# BATT_DISP_v7.net
KiCad netlist of a schematic drawn in EAGLE
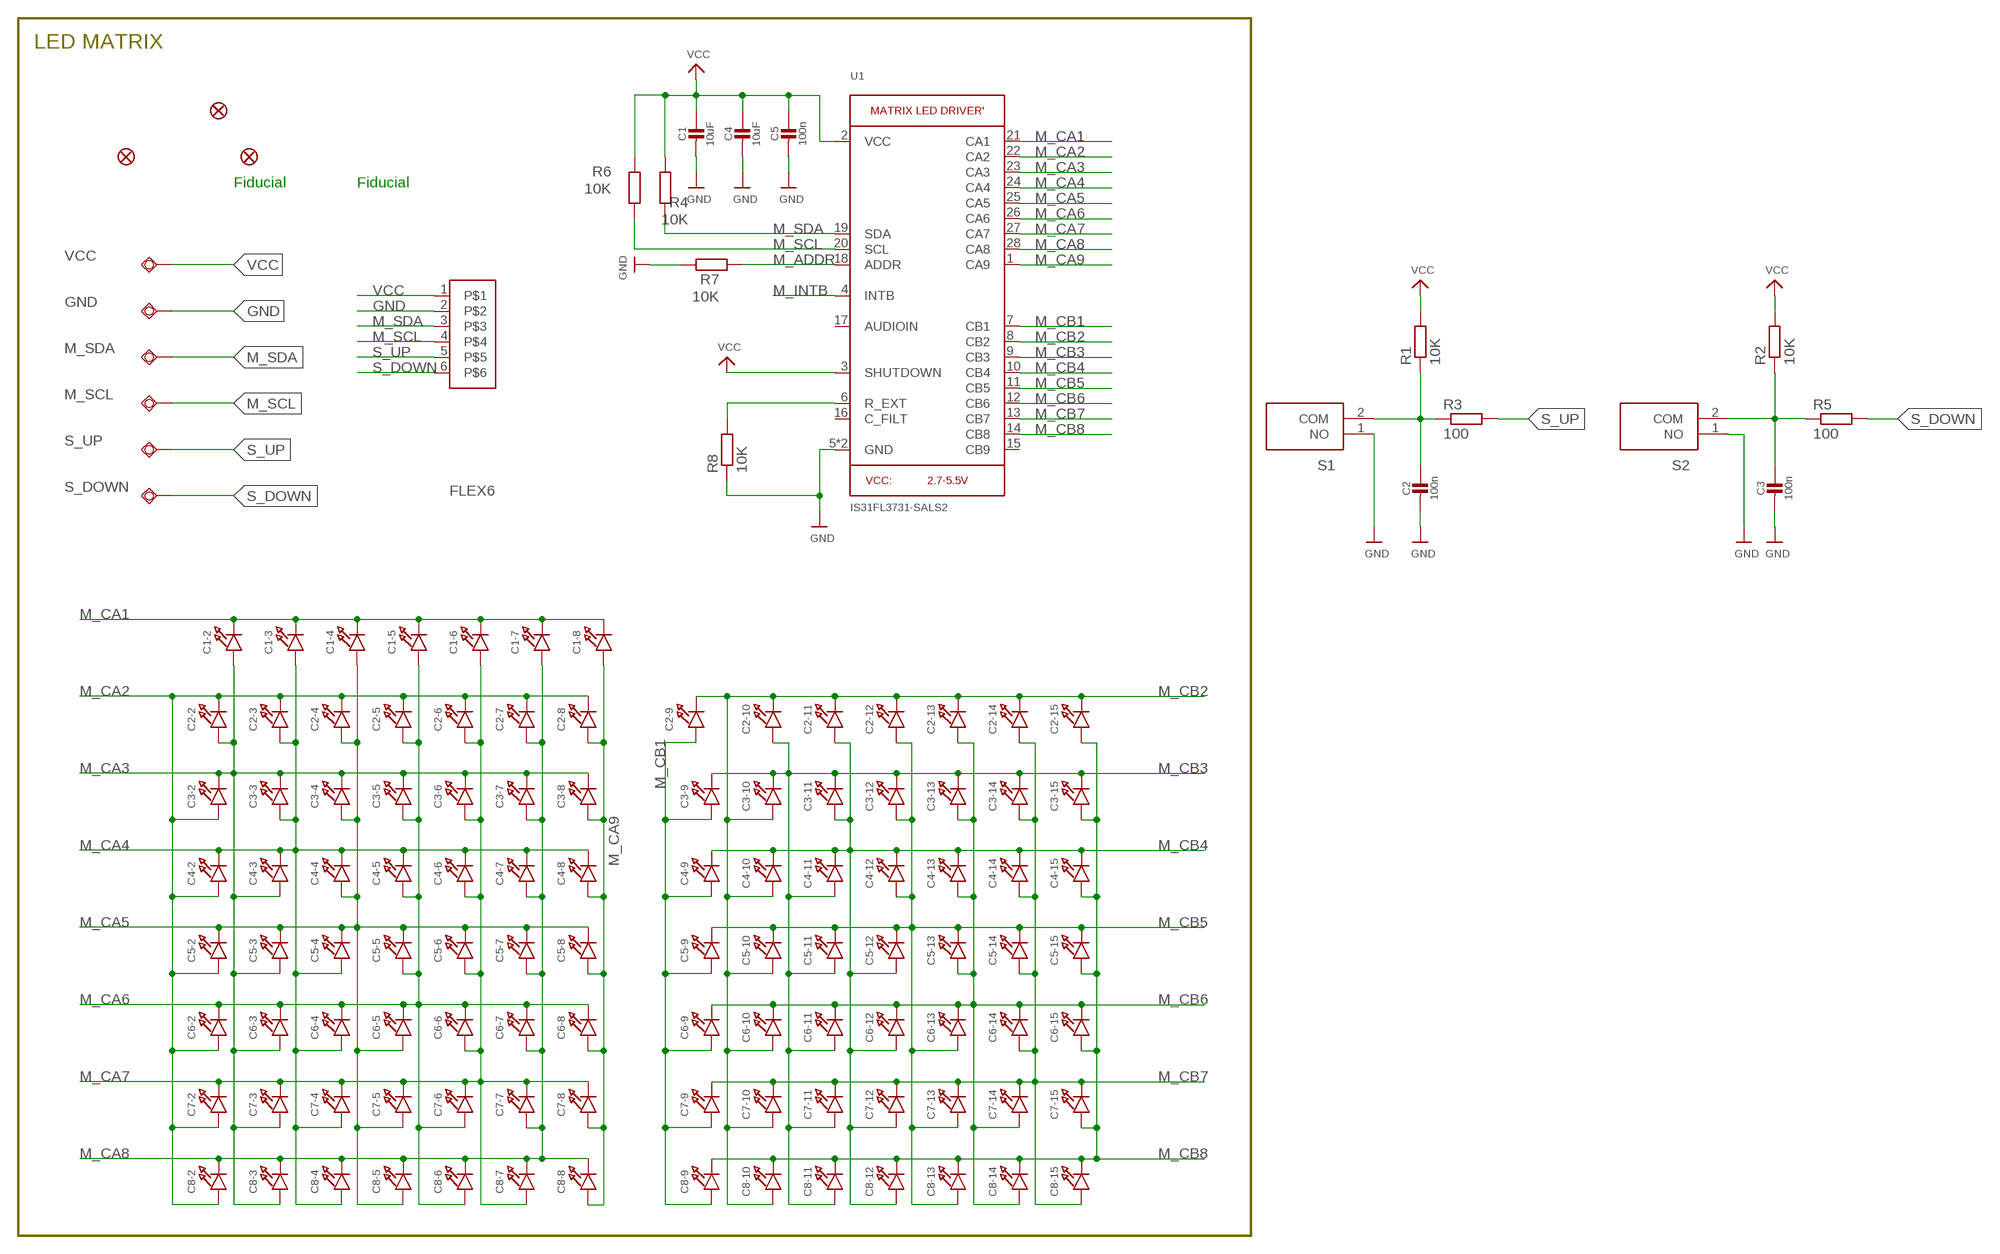
[diagram p0: schematic, sheet 1]

(export (version "E")
  (design (tool "Eeschema 10.0.6"))
  (components
    (comp (ref "C1")
      (value "10uF")
      (footprint "eagle-import:0805-NO")
      (libsource (lib "eagle-import") (part "CAP_CERAMIC0805-NOOUTLINE"))
    )
    (comp (ref "C1-2")
      (value "LED0402_NOOUTLINE")
      (footprint "eagle-import:CHIPLED_0402_NOOUTLINE")
      (libsource (lib "eagle-import") (part "LED0402_NOOUTLINE"))
    )
    (comp (ref "C1-3")
      (value "LED0402_NOOUTLINE")
      (footprint "eagle-import:CHIPLED_0402_NOOUTLINE")
      (libsource (lib "eagle-import") (part "LED0402_NOOUTLINE"))
    )
    (comp (ref "C1-4")
      (value "LED0402_NOOUTLINE")
      (footprint "eagle-import:CHIPLED_0402_NOOUTLINE")
      (libsource (lib "eagle-import") (part "LED0402_NOOUTLINE"))
    )
    (comp (ref "C1-5")
      (value "LED0402_NOOUTLINE")
      (footprint "eagle-import:CHIPLED_0402_NOOUTLINE")
      (libsource (lib "eagle-import") (part "LED0402_NOOUTLINE"))
    )
    (comp (ref "C1-6")
      (value "LED0402_NOOUTLINE")
      (footprint "eagle-import:CHIPLED_0402_NOOUTLINE")
      (libsource (lib "eagle-import") (part "LED0402_NOOUTLINE"))
    )
    (comp (ref "C1-7")
      (value "LED0402_NOOUTLINE")
      (footprint "eagle-import:CHIPLED_0402_NOOUTLINE")
      (libsource (lib "eagle-import") (part "LED0402_NOOUTLINE"))
    )
    (comp (ref "C1-8")
      (value "LED0402_NOOUTLINE")
      (footprint "eagle-import:CHIPLED_0402_NOOUTLINE")
      (libsource (lib "eagle-import") (part "LED0402_NOOUTLINE"))
    )
    (comp (ref "C2")
      (value "100n")
      (footprint "eagle-import:0805-NO")
      (libsource (lib "eagle-import") (part "CAP_CERAMIC0805-NOOUTLINE"))
    )
    (comp (ref "C2-2")
      (value "LED0402_NOOUTLINE")
      (footprint "eagle-import:CHIPLED_0402_NOOUTLINE")
      (libsource (lib "eagle-import") (part "LED0402_NOOUTLINE"))
    )
    (comp (ref "C2-3")
      (value "LED0402_NOOUTLINE")
      (footprint "eagle-import:CHIPLED_0402_NOOUTLINE")
      (libsource (lib "eagle-import") (part "LED0402_NOOUTLINE"))
    )
    (comp (ref "C2-4")
      (value "LED0402_NOOUTLINE")
      (footprint "eagle-import:CHIPLED_0402_NOOUTLINE")
      (libsource (lib "eagle-import") (part "LED0402_NOOUTLINE"))
    )
    (comp (ref "C2-5")
      (value "LED0402_NOOUTLINE")
      (footprint "eagle-import:CHIPLED_0402_NOOUTLINE")
      (libsource (lib "eagle-import") (part "LED0402_NOOUTLINE"))
    )
    (comp (ref "C2-6")
      (value "LED0402_NOOUTLINE")
      (footprint "eagle-import:CHIPLED_0402_NOOUTLINE")
      (libsource (lib "eagle-import") (part "LED0402_NOOUTLINE"))
    )
    (comp (ref "C2-7")
      (value "LED0402_NOOUTLINE")
      (footprint "eagle-import:CHIPLED_0402_NOOUTLINE")
      (libsource (lib "eagle-import") (part "LED0402_NOOUTLINE"))
    )
    (comp (ref "C2-8")
      (value "LED0402_NOOUTLINE")
      (footprint "eagle-import:CHIPLED_0402_NOOUTLINE")
      (libsource (lib "eagle-import") (part "LED0402_NOOUTLINE"))
    )
    (comp (ref "C2-9")
      (value "LED0402_NOOUTLINE")
      (footprint "eagle-import:CHIPLED_0402_NOOUTLINE")
      (libsource (lib "eagle-import") (part "LED0402_NOOUTLINE"))
    )
    (comp (ref "C2-10")
      (value "LED0402_NOOUTLINE")
      (footprint "eagle-import:CHIPLED_0402_NOOUTLINE")
      (libsource (lib "eagle-import") (part "LED0402_NOOUTLINE"))
    )
    (comp (ref "C2-11")
      (value "LED0402_NOOUTLINE")
      (footprint "eagle-import:CHIPLED_0402_NOOUTLINE")
      (libsource (lib "eagle-import") (part "LED0402_NOOUTLINE"))
    )
    (comp (ref "C2-12")
      (value "LED0402_NOOUTLINE")
      (footprint "eagle-import:CHIPLED_0402_NOOUTLINE")
      (libsource (lib "eagle-import") (part "LED0402_NOOUTLINE"))
    )
    (comp (ref "C2-13")
      (value "LED0402_NOOUTLINE")
      (footprint "eagle-import:CHIPLED_0402_NOOUTLINE")
      (libsource (lib "eagle-import") (part "LED0402_NOOUTLINE"))
    )
    (comp (ref "C2-14")
      (value "LED0402_NOOUTLINE")
      (footprint "eagle-import:CHIPLED_0402_NOOUTLINE")
      (libsource (lib "eagle-import") (part "LED0402_NOOUTLINE"))
    )
    (comp (ref "C2-15")
      (value "LED0402_NOOUTLINE")
      (footprint "eagle-import:CHIPLED_0402_NOOUTLINE")
      (libsource (lib "eagle-import") (part "LED0402_NOOUTLINE"))
    )
    (comp (ref "C3")
      (value "100n")
      (footprint "eagle-import:0805-NO")
      (libsource (lib "eagle-import") (part "CAP_CERAMIC0805-NOOUTLINE"))
    )
    (comp (ref "C3-2")
      (value "LED0402_NOOUTLINE")
      (footprint "eagle-import:CHIPLED_0402_NOOUTLINE")
      (libsource (lib "eagle-import") (part "LED0402_NOOUTLINE"))
    )
    (comp (ref "C3-3")
      (value "LED0402_NOOUTLINE")
      (footprint "eagle-import:CHIPLED_0402_NOOUTLINE")
      (libsource (lib "eagle-import") (part "LED0402_NOOUTLINE"))
    )
    (comp (ref "C3-4")
      (value "LED0402_NOOUTLINE")
      (footprint "eagle-import:CHIPLED_0402_NOOUTLINE")
      (libsource (lib "eagle-import") (part "LED0402_NOOUTLINE"))
    )
    (comp (ref "C3-5")
      (value "LED0402_NOOUTLINE")
      (footprint "eagle-import:CHIPLED_0402_NOOUTLINE")
      (libsource (lib "eagle-import") (part "LED0402_NOOUTLINE"))
    )
    (comp (ref "C3-6")
      (value "LED0402_NOOUTLINE")
      (footprint "eagle-import:CHIPLED_0402_NOOUTLINE")
      (libsource (lib "eagle-import") (part "LED0402_NOOUTLINE"))
    )
    (comp (ref "C3-7")
      (value "LED0402_NOOUTLINE")
      (footprint "eagle-import:CHIPLED_0402_NOOUTLINE")
      (libsource (lib "eagle-import") (part "LED0402_NOOUTLINE"))
    )
    (comp (ref "C3-8")
      (value "LED0402_NOOUTLINE")
      (footprint "eagle-import:CHIPLED_0402_NOOUTLINE")
      (libsource (lib "eagle-import") (part "LED0402_NOOUTLINE"))
    )
    (comp (ref "C3-9")
      (value "LED0402_NOOUTLINE")
      (footprint "eagle-import:CHIPLED_0402_NOOUTLINE")
      (libsource (lib "eagle-import") (part "LED0402_NOOUTLINE"))
    )
    (comp (ref "C3-10")
      (value "LED0402_NOOUTLINE")
      (footprint "eagle-import:CHIPLED_0402_NOOUTLINE")
      (libsource (lib "eagle-import") (part "LED0402_NOOUTLINE"))
    )
    (comp (ref "C3-11")
      (value "LED0402_NOOUTLINE")
      (footprint "eagle-import:CHIPLED_0402_NOOUTLINE")
      (libsource (lib "eagle-import") (part "LED0402_NOOUTLINE"))
    )
    (comp (ref "C3-12")
      (value "LED0402_NOOUTLINE")
      (footprint "eagle-import:CHIPLED_0402_NOOUTLINE")
      (libsource (lib "eagle-import") (part "LED0402_NOOUTLINE"))
    )
    (comp (ref "C3-13")
      (value "LED0402_NOOUTLINE")
      (footprint "eagle-import:CHIPLED_0402_NOOUTLINE")
      (libsource (lib "eagle-import") (part "LED0402_NOOUTLINE"))
    )
    (comp (ref "C3-14")
      (value "LED0402_NOOUTLINE")
      (footprint "eagle-import:CHIPLED_0402_NOOUTLINE")
      (libsource (lib "eagle-import") (part "LED0402_NOOUTLINE"))
    )
    (comp (ref "C3-15")
      (value "LED0402_NOOUTLINE")
      (footprint "eagle-import:CHIPLED_0402_NOOUTLINE")
      (libsource (lib "eagle-import") (part "LED0402_NOOUTLINE"))
    )
    (comp (ref "C4")
      (value "10uF")
      (footprint "eagle-import:0805-NO")
      (libsource (lib "eagle-import") (part "CAP_CERAMIC0805-NOOUTLINE"))
    )
    (comp (ref "C4-2")
      (value "LED0402_NOOUTLINE")
      (footprint "eagle-import:CHIPLED_0402_NOOUTLINE")
      (libsource (lib "eagle-import") (part "LED0402_NOOUTLINE"))
    )
    (comp (ref "C4-3")
      (value "LED0402_NOOUTLINE")
      (footprint "eagle-import:CHIPLED_0402_NOOUTLINE")
      (libsource (lib "eagle-import") (part "LED0402_NOOUTLINE"))
    )
    (comp (ref "C4-4")
      (value "LED0402_NOOUTLINE")
      (footprint "eagle-import:CHIPLED_0402_NOOUTLINE")
      (libsource (lib "eagle-import") (part "LED0402_NOOUTLINE"))
    )
    (comp (ref "C4-5")
      (value "LED0402_NOOUTLINE")
      (footprint "eagle-import:CHIPLED_0402_NOOUTLINE")
      (libsource (lib "eagle-import") (part "LED0402_NOOUTLINE"))
    )
    (comp (ref "C4-6")
      (value "LED0402_NOOUTLINE")
      (footprint "eagle-import:CHIPLED_0402_NOOUTLINE")
      (libsource (lib "eagle-import") (part "LED0402_NOOUTLINE"))
    )
    (comp (ref "C4-7")
      (value "LED0402_NOOUTLINE")
      (footprint "eagle-import:CHIPLED_0402_NOOUTLINE")
      (libsource (lib "eagle-import") (part "LED0402_NOOUTLINE"))
    )
    (comp (ref "C4-8")
      (value "LED0402_NOOUTLINE")
      (footprint "eagle-import:CHIPLED_0402_NOOUTLINE")
      (libsource (lib "eagle-import") (part "LED0402_NOOUTLINE"))
    )
    (comp (ref "C4-9")
      (value "LED0402_NOOUTLINE")
      (footprint "eagle-import:CHIPLED_0402_NOOUTLINE")
      (libsource (lib "eagle-import") (part "LED0402_NOOUTLINE"))
    )
    (comp (ref "C4-10")
      (value "LED0402_NOOUTLINE")
      (footprint "eagle-import:CHIPLED_0402_NOOUTLINE")
      (libsource (lib "eagle-import") (part "LED0402_NOOUTLINE"))
    )
    (comp (ref "C4-11")
      (value "LED0402_NOOUTLINE")
      (footprint "eagle-import:CHIPLED_0402_NOOUTLINE")
      (libsource (lib "eagle-import") (part "LED0402_NOOUTLINE"))
    )
    (comp (ref "C4-12")
      (value "LED0402_NOOUTLINE")
      (footprint "eagle-import:CHIPLED_0402_NOOUTLINE")
      (libsource (lib "eagle-import") (part "LED0402_NOOUTLINE"))
    )
    (comp (ref "C4-13")
      (value "LED0402_NOOUTLINE")
      (footprint "eagle-import:CHIPLED_0402_NOOUTLINE")
      (libsource (lib "eagle-import") (part "LED0402_NOOUTLINE"))
    )
    (comp (ref "C4-14")
      (value "LED0402_NOOUTLINE")
      (footprint "eagle-import:CHIPLED_0402_NOOUTLINE")
      (libsource (lib "eagle-import") (part "LED0402_NOOUTLINE"))
    )
    (comp (ref "C4-15")
      (value "LED0402_NOOUTLINE")
      (footprint "eagle-import:CHIPLED_0402_NOOUTLINE")
      (libsource (lib "eagle-import") (part "LED0402_NOOUTLINE"))
    )
    (comp (ref "C5")
      (value "100n")
      (footprint "eagle-import:0805-NO")
      (libsource (lib "eagle-import") (part "CAP_CERAMIC0805-NOOUTLINE"))
    )
    (comp (ref "C5-2")
      (value "LED0402_NOOUTLINE")
      (footprint "eagle-import:CHIPLED_0402_NOOUTLINE")
      (libsource (lib "eagle-import") (part "LED0402_NOOUTLINE"))
    )
    (comp (ref "C5-3")
      (value "LED0402_NOOUTLINE")
      (footprint "eagle-import:CHIPLED_0402_NOOUTLINE")
      (libsource (lib "eagle-import") (part "LED0402_NOOUTLINE"))
    )
    (comp (ref "C5-4")
      (value "LED0402_NOOUTLINE")
      (footprint "eagle-import:CHIPLED_0402_NOOUTLINE")
      (libsource (lib "eagle-import") (part "LED0402_NOOUTLINE"))
    )
    (comp (ref "C5-5")
      (value "LED0402_NOOUTLINE")
      (footprint "eagle-import:CHIPLED_0402_NOOUTLINE")
      (libsource (lib "eagle-import") (part "LED0402_NOOUTLINE"))
    )
    (comp (ref "C5-6")
      (value "LED0402_NOOUTLINE")
      (footprint "eagle-import:CHIPLED_0402_NOOUTLINE")
      (libsource (lib "eagle-import") (part "LED0402_NOOUTLINE"))
    )
    (comp (ref "C5-7")
      (value "LED0402_NOOUTLINE")
      (footprint "eagle-import:CHIPLED_0402_NOOUTLINE")
      (libsource (lib "eagle-import") (part "LED0402_NOOUTLINE"))
    )
    (comp (ref "C5-8")
      (value "LED0402_NOOUTLINE")
      (footprint "eagle-import:CHIPLED_0402_NOOUTLINE")
      (libsource (lib "eagle-import") (part "LED0402_NOOUTLINE"))
    )
    (comp (ref "C5-9")
      (value "LED0402_NOOUTLINE")
      (footprint "eagle-import:CHIPLED_0402_NOOUTLINE")
      (libsource (lib "eagle-import") (part "LED0402_NOOUTLINE"))
    )
    (comp (ref "C5-10")
      (value "LED0402_NOOUTLINE")
      (footprint "eagle-import:CHIPLED_0402_NOOUTLINE")
      (libsource (lib "eagle-import") (part "LED0402_NOOUTLINE"))
    )
    (comp (ref "C5-11")
      (value "LED0402_NOOUTLINE")
      (footprint "eagle-import:CHIPLED_0402_NOOUTLINE")
      (libsource (lib "eagle-import") (part "LED0402_NOOUTLINE"))
    )
    (comp (ref "C5-12")
      (value "LED0402_NOOUTLINE")
      (footprint "eagle-import:CHIPLED_0402_NOOUTLINE")
      (libsource (lib "eagle-import") (part "LED0402_NOOUTLINE"))
    )
    (comp (ref "C5-13")
      (value "LED0402_NOOUTLINE")
      (footprint "eagle-import:CHIPLED_0402_NOOUTLINE")
      (libsource (lib "eagle-import") (part "LED0402_NOOUTLINE"))
    )
    (comp (ref "C5-14")
      (value "LED0402_NOOUTLINE")
      (footprint "eagle-import:CHIPLED_0402_NOOUTLINE")
      (libsource (lib "eagle-import") (part "LED0402_NOOUTLINE"))
    )
    (comp (ref "C5-15")
      (value "LED0402_NOOUTLINE")
      (footprint "eagle-import:CHIPLED_0402_NOOUTLINE")
      (libsource (lib "eagle-import") (part "LED0402_NOOUTLINE"))
    )
    (comp (ref "C6-2")
      (value "LED0402_NOOUTLINE")
      (footprint "eagle-import:CHIPLED_0402_NOOUTLINE")
      (libsource (lib "eagle-import") (part "LED0402_NOOUTLINE"))
    )
    (comp (ref "C6-3")
      (value "LED0402_NOOUTLINE")
      (footprint "eagle-import:CHIPLED_0402_NOOUTLINE")
      (libsource (lib "eagle-import") (part "LED0402_NOOUTLINE"))
    )
    (comp (ref "C6-4")
      (value "LED0402_NOOUTLINE")
      (footprint "eagle-import:CHIPLED_0402_NOOUTLINE")
      (libsource (lib "eagle-import") (part "LED0402_NOOUTLINE"))
    )
    (comp (ref "C6-5")
      (value "LED0402_NOOUTLINE")
      (footprint "eagle-import:CHIPLED_0402_NOOUTLINE")
      (libsource (lib "eagle-import") (part "LED0402_NOOUTLINE"))
    )
    (comp (ref "C6-6")
      (value "LED0402_NOOUTLINE")
      (footprint "eagle-import:CHIPLED_0402_NOOUTLINE")
      (libsource (lib "eagle-import") (part "LED0402_NOOUTLINE"))
    )
    (comp (ref "C6-7")
      (value "LED0402_NOOUTLINE")
      (footprint "eagle-import:CHIPLED_0402_NOOUTLINE")
      (libsource (lib "eagle-import") (part "LED0402_NOOUTLINE"))
    )
    (comp (ref "C6-8")
      (value "LED0402_NOOUTLINE")
      (footprint "eagle-import:CHIPLED_0402_NOOUTLINE")
      (libsource (lib "eagle-import") (part "LED0402_NOOUTLINE"))
    )
    (comp (ref "C6-9")
      (value "LED0402_NOOUTLINE")
      (footprint "eagle-import:CHIPLED_0402_NOOUTLINE")
      (libsource (lib "eagle-import") (part "LED0402_NOOUTLINE"))
    )
    (comp (ref "C6-10")
      (value "LED0402_NOOUTLINE")
      (footprint "eagle-import:CHIPLED_0402_NOOUTLINE")
      (libsource (lib "eagle-import") (part "LED0402_NOOUTLINE"))
    )
    (comp (ref "C6-11")
      (value "LED0402_NOOUTLINE")
      (footprint "eagle-import:CHIPLED_0402_NOOUTLINE")
      (libsource (lib "eagle-import") (part "LED0402_NOOUTLINE"))
    )
    (comp (ref "C6-12")
      (value "LED0402_NOOUTLINE")
      (footprint "eagle-import:CHIPLED_0402_NOOUTLINE")
      (libsource (lib "eagle-import") (part "LED0402_NOOUTLINE"))
    )
    (comp (ref "C6-13")
      (value "LED0402_NOOUTLINE")
      (footprint "eagle-import:CHIPLED_0402_NOOUTLINE")
      (libsource (lib "eagle-import") (part "LED0402_NOOUTLINE"))
    )
    (comp (ref "C6-14")
      (value "LED0402_NOOUTLINE")
      (footprint "eagle-import:CHIPLED_0402_NOOUTLINE")
      (libsource (lib "eagle-import") (part "LED0402_NOOUTLINE"))
    )
    (comp (ref "C6-15")
      (value "LED0402_NOOUTLINE")
      (footprint "eagle-import:CHIPLED_0402_NOOUTLINE")
      (libsource (lib "eagle-import") (part "LED0402_NOOUTLINE"))
    )
    (comp (ref "C7-2")
      (value "LED0402_NOOUTLINE")
      (footprint "eagle-import:CHIPLED_0402_NOOUTLINE")
      (libsource (lib "eagle-import") (part "LED0402_NOOUTLINE"))
    )
    (comp (ref "C7-3")
      (value "LED0402_NOOUTLINE")
      (footprint "eagle-import:CHIPLED_0402_NOOUTLINE")
      (libsource (lib "eagle-import") (part "LED0402_NOOUTLINE"))
    )
    (comp (ref "C7-4")
      (value "LED0402_NOOUTLINE")
      (footprint "eagle-import:CHIPLED_0402_NOOUTLINE")
      (libsource (lib "eagle-import") (part "LED0402_NOOUTLINE"))
    )
    (comp (ref "C7-5")
      (value "LED0402_NOOUTLINE")
      (footprint "eagle-import:CHIPLED_0402_NOOUTLINE")
      (libsource (lib "eagle-import") (part "LED0402_NOOUTLINE"))
    )
    (comp (ref "C7-6")
      (value "LED0402_NOOUTLINE")
      (footprint "eagle-import:CHIPLED_0402_NOOUTLINE")
      (libsource (lib "eagle-import") (part "LED0402_NOOUTLINE"))
    )
    (comp (ref "C7-7")
      (value "LED0402_NOOUTLINE")
      (footprint "eagle-import:CHIPLED_0402_NOOUTLINE")
      (libsource (lib "eagle-import") (part "LED0402_NOOUTLINE"))
    )
    (comp (ref "C7-8")
      (value "LED0402_NOOUTLINE")
      (footprint "eagle-import:CHIPLED_0402_NOOUTLINE")
      (libsource (lib "eagle-import") (part "LED0402_NOOUTLINE"))
    )
    (comp (ref "C7-9")
      (value "LED0402_NOOUTLINE")
      (footprint "eagle-import:CHIPLED_0402_NOOUTLINE")
      (libsource (lib "eagle-import") (part "LED0402_NOOUTLINE"))
    )
    (comp (ref "C7-10")
      (value "LED0402_NOOUTLINE")
      (footprint "eagle-import:CHIPLED_0402_NOOUTLINE")
      (libsource (lib "eagle-import") (part "LED0402_NOOUTLINE"))
    )
    (comp (ref "C7-11")
      (value "LED0402_NOOUTLINE")
      (footprint "eagle-import:CHIPLED_0402_NOOUTLINE")
      (libsource (lib "eagle-import") (part "LED0402_NOOUTLINE"))
    )
    (comp (ref "C7-12")
      (value "LED0402_NOOUTLINE")
      (footprint "eagle-import:CHIPLED_0402_NOOUTLINE")
      (libsource (lib "eagle-import") (part "LED0402_NOOUTLINE"))
    )
    (comp (ref "C7-13")
      (value "LED0402_NOOUTLINE")
      (footprint "eagle-import:CHIPLED_0402_NOOUTLINE")
      (libsource (lib "eagle-import") (part "LED0402_NOOUTLINE"))
    )
    (comp (ref "C7-14")
      (value "LED0402_NOOUTLINE")
      (footprint "eagle-import:CHIPLED_0402_NOOUTLINE")
      (libsource (lib "eagle-import") (part "LED0402_NOOUTLINE"))
    )
    (comp (ref "C7-15")
      (value "LED0402_NOOUTLINE")
      (footprint "eagle-import:CHIPLED_0402_NOOUTLINE")
      (libsource (lib "eagle-import") (part "LED0402_NOOUTLINE"))
    )
    (comp (ref "C8-2")
      (value "LED0402_NOOUTLINE")
      (footprint "eagle-import:CHIPLED_0402_NOOUTLINE")
      (libsource (lib "eagle-import") (part "LED0402_NOOUTLINE"))
    )
    (comp (ref "C8-3")
      (value "LED0402_NOOUTLINE")
      (footprint "eagle-import:CHIPLED_0402_NOOUTLINE")
      (libsource (lib "eagle-import") (part "LED0402_NOOUTLINE"))
    )
    (comp (ref "C8-4")
      (value "LED0402_NOOUTLINE")
      (footprint "eagle-import:CHIPLED_0402_NOOUTLINE")
      (libsource (lib "eagle-import") (part "LED0402_NOOUTLINE"))
    )
    (comp (ref "C8-5")
      (value "LED0402_NOOUTLINE")
      (footprint "eagle-import:CHIPLED_0402_NOOUTLINE")
      (libsource (lib "eagle-import") (part "LED0402_NOOUTLINE"))
    )
    (comp (ref "C8-6")
      (value "LED0402_NOOUTLINE")
      (footprint "eagle-import:CHIPLED_0402_NOOUTLINE")
      (libsource (lib "eagle-import") (part "LED0402_NOOUTLINE"))
    )
    (comp (ref "C8-7")
      (value "LED0402_NOOUTLINE")
      (footprint "eagle-import:CHIPLED_0402_NOOUTLINE")
      (libsource (lib "eagle-import") (part "LED0402_NOOUTLINE"))
    )
    (comp (ref "C8-8")
      (value "LED0402_NOOUTLINE")
      (footprint "eagle-import:CHIPLED_0402_NOOUTLINE")
      (libsource (lib "eagle-import") (part "LED0402_NOOUTLINE"))
    )
    (comp (ref "C8-9")
      (value "LED0402_NOOUTLINE")
      (footprint "eagle-import:CHIPLED_0402_NOOUTLINE")
      (libsource (lib "eagle-import") (part "LED0402_NOOUTLINE"))
    )
    (comp (ref "C8-10")
      (value "LED0402_NOOUTLINE")
      (footprint "eagle-import:CHIPLED_0402_NOOUTLINE")
      (libsource (lib "eagle-import") (part "LED0402_NOOUTLINE"))
    )
    (comp (ref "C8-11")
      (value "LED0402_NOOUTLINE")
      (footprint "eagle-import:CHIPLED_0402_NOOUTLINE")
      (libsource (lib "eagle-import") (part "LED0402_NOOUTLINE"))
    )
    (comp (ref "C8-12")
      (value "LED0402_NOOUTLINE")
      (footprint "eagle-import:CHIPLED_0402_NOOUTLINE")
      (libsource (lib "eagle-import") (part "LED0402_NOOUTLINE"))
    )
    (comp (ref "C8-13")
      (value "LED0402_NOOUTLINE")
      (footprint "eagle-import:CHIPLED_0402_NOOUTLINE")
      (libsource (lib "eagle-import") (part "LED0402_NOOUTLINE"))
    )
    (comp (ref "C8-14")
      (value "LED0402_NOOUTLINE")
      (footprint "eagle-import:CHIPLED_0402_NOOUTLINE")
      (libsource (lib "eagle-import") (part "LED0402_NOOUTLINE"))
    )
    (comp (ref "C8-15")
      (value "LED0402_NOOUTLINE")
      (footprint "eagle-import:CHIPLED_0402_NOOUTLINE")
      (libsource (lib "eagle-import") (part "LED0402_NOOUTLINE"))
    )
    (comp (ref "FD1")
      (value "FIDUCIALUFIDUCIAL")
      (footprint "eagle-import:FIDUCIAL-MICRO")
      (libsource (lib "eagle-import") (part "FIDUCIALUFIDUCIAL"))
    )
    (comp (ref "FD2")
      (value "FIDUCIAL\"\"")
      (footprint "eagle-import:FIDUCIAL_1MM")
      (libsource (lib "eagle-import") (part "FIDUCIAL{dblquote}{dblquote}"))
    )
    (comp (ref "FD3")
      (value "FIDUCIAL\"\"")
      (footprint "eagle-import:FIDUCIAL_1MM")
      (libsource (lib "eagle-import") (part "FIDUCIAL{dblquote}{dblquote}"))
    )
    (comp (ref "GND")
      (value "TESTPAD_TPSQB1,27")
      (footprint "eagle-import:TESTPAD_B1,27")
      (libsource (lib "eagle-import") (part "TESTPAD_TPSQB1,27"))
    )
    (comp (ref "K1")
      (value "FLEX6")
      (footprint "eagle-import:FLEX6")
      (libsource (lib "eagle-import") (part "FLEX6"))
    )
    (comp (ref "M_SCL")
      (value "TESTPAD_TPSQB1,27")
      (footprint "eagle-import:TESTPAD_B1,27")
      (libsource (lib "eagle-import") (part "TESTPAD_TPSQB1,27"))
    )
    (comp (ref "M_SDA")
      (value "TESTPAD_TPSQB1,27")
      (footprint "eagle-import:TESTPAD_B1,27")
      (libsource (lib "eagle-import") (part "TESTPAD_TPSQB1,27"))
    )
    (comp (ref "R1")
      (value "10K")
      (footprint "eagle-import:R0603")
      (libsource (lib "eagle-import") (part "R-EU_R0603"))
    )
    (comp (ref "R2")
      (value "10K")
      (footprint "eagle-import:R0603")
      (libsource (lib "eagle-import") (part "R-EU_R0603"))
    )
    (comp (ref "R3")
      (value "100")
      (footprint "eagle-import:R0603")
      (libsource (lib "eagle-import") (part "R-EU_R0603"))
    )
    (comp (ref "R4")
      (value "10K")
      (footprint "eagle-import:R0603")
      (libsource (lib "eagle-import") (part "R-EU_R0603"))
    )
    (comp (ref "R5")
      (value "100")
      (footprint "eagle-import:R0603")
      (libsource (lib "eagle-import") (part "R-EU_R0603"))
    )
    (comp (ref "R6")
      (value "10K")
      (footprint "eagle-import:R0603")
      (libsource (lib "eagle-import") (part "R-EU_R0603"))
    )
    (comp (ref "R7")
      (value "10K")
      (footprint "eagle-import:R0603")
      (libsource (lib "eagle-import") (part "R-EU_R0603"))
    )
    (comp (ref "R8")
      (value "10K")
      (footprint "eagle-import:R0603")
      (libsource (lib "eagle-import") (part "R-EU_R0603"))
    )
    (comp (ref "S1")
      (value "KXT311LHS")
      (footprint "eagle-import:KXT311LHS")
      (fields (field (name "MOUSER_PART_NUMBER") "611-KXT311LHS"))
      (libsource (lib "eagle-import") (part "KXT311LHS"))
    )
    (comp (ref "S2")
      (value "KXT311LHS")
      (footprint "eagle-import:KXT311LHS")
      (fields (field (name "MOUSER_PART_NUMBER") "611-KXT311LHS"))
      (libsource (lib "eagle-import") (part "KXT311LHS"))
    )
    (comp (ref "S_DOWN")
      (value "TESTPAD_TPSQB1,27")
      (footprint "eagle-import:TESTPAD_B1,27")
      (libsource (lib "eagle-import") (part "TESTPAD_TPSQB1,27"))
    )
    (comp (ref "S_UP")
      (value "TESTPAD_TPSQB1,27")
      (footprint "eagle-import:TESTPAD_B1,27")
      (libsource (lib "eagle-import") (part "TESTPAD_TPSQB1,27"))
    )
    (comp (ref "U1")
      (value "IS31FL3731-SALS2")
      (footprint "eagle-import:QFN28_4MM_0.4MM")
      (libsource (lib "eagle-import") (part "IS31FL3731QFN"))
    )
    (comp (ref "VCC")
      (value "TESTPAD_TPSQB1,27")
      (footprint "eagle-import:TESTPAD_B1,27")
      (libsource (lib "eagle-import") (part "TESTPAD_TPSQB1,27"))
    )
  )
  (nets
    (net (code "1") (name "/M_ADDR") (class "Default")
      (node (ref "R7") (pin "1") (pinfunction "1_1") (pintype "passive"))
      (node (ref "U1") (pin "18") (pinfunction "ADDR_18") (pintype "bidirectional"))
    )
    (net (code "2") (name "/M_CA1") (class "Default")
      (node (ref "C1-2") (pin "C") (pinfunction "C_C") (pintype "passive"))
      (node (ref "C1-3") (pin "C") (pinfunction "C_C") (pintype "passive"))
      (node (ref "C1-4") (pin "C") (pinfunction "C_C") (pintype "passive"))
      (node (ref "C1-5") (pin "C") (pinfunction "C_C") (pintype "passive"))
      (node (ref "C1-6") (pin "C") (pinfunction "C_C") (pintype "passive"))
      (node (ref "C1-7") (pin "C") (pinfunction "C_C") (pintype "passive"))
      (node (ref "C1-8") (pin "C") (pinfunction "C_C") (pintype "passive"))
      (node (ref "U1") (pin "21") (pinfunction "CA1_21") (pintype "bidirectional"))
    )
    (net (code "3") (name "/M_CA2") (class "Default")
      (node (ref "C2-2") (pin "C") (pinfunction "C_C") (pintype "passive"))
      (node (ref "C2-3") (pin "C") (pinfunction "C_C") (pintype "passive"))
      (node (ref "C2-4") (pin "C") (pinfunction "C_C") (pintype "passive"))
      (node (ref "C2-5") (pin "C") (pinfunction "C_C") (pintype "passive"))
      (node (ref "C2-6") (pin "C") (pinfunction "C_C") (pintype "passive"))
      (node (ref "C2-7") (pin "C") (pinfunction "C_C") (pintype "passive"))
      (node (ref "C2-8") (pin "C") (pinfunction "C_C") (pintype "passive"))
      (node (ref "C3-2") (pin "A") (pinfunction "A_A") (pintype "passive"))
      (node (ref "C4-2") (pin "A") (pinfunction "A_A") (pintype "passive"))
      (node (ref "C5-2") (pin "A") (pinfunction "A_A") (pintype "passive"))
      (node (ref "C6-2") (pin "A") (pinfunction "A_A") (pintype "passive"))
      (node (ref "C7-2") (pin "A") (pinfunction "A_A") (pintype "passive"))
      (node (ref "C8-2") (pin "A") (pinfunction "A_A") (pintype "passive"))
      (node (ref "U1") (pin "22") (pinfunction "CA2_22") (pintype "bidirectional"))
    )
    (net (code "4") (name "/M_CA3") (class "Default")
      (node (ref "C1-2") (pin "A") (pinfunction "A_A") (pintype "passive"))
      (node (ref "C2-2") (pin "A") (pinfunction "A_A") (pintype "passive"))
      (node (ref "C3-2") (pin "C") (pinfunction "C_C") (pintype "passive"))
      (node (ref "C3-3") (pin "C") (pinfunction "C_C") (pintype "passive"))
      (node (ref "C3-4") (pin "C") (pinfunction "C_C") (pintype "passive"))
      (node (ref "C3-5") (pin "C") (pinfunction "C_C") (pintype "passive"))
      (node (ref "C3-6") (pin "C") (pinfunction "C_C") (pintype "passive"))
      (node (ref "C3-7") (pin "C") (pinfunction "C_C") (pintype "passive"))
      (node (ref "C3-8") (pin "C") (pinfunction "C_C") (pintype "passive"))
      (node (ref "C4-3") (pin "A") (pinfunction "A_A") (pintype "passive"))
      (node (ref "C5-3") (pin "A") (pinfunction "A_A") (pintype "passive"))
      (node (ref "C6-3") (pin "A") (pinfunction "A_A") (pintype "passive"))
      (node (ref "C7-3") (pin "A") (pinfunction "A_A") (pintype "passive"))
      (node (ref "C8-3") (pin "A") (pinfunction "A_A") (pintype "passive"))
      (node (ref "U1") (pin "23") (pinfunction "CA3_23") (pintype "bidirectional"))
    )
    (net (code "5") (name "/M_CA4") (class "Default")
      (node (ref "C1-3") (pin "A") (pinfunction "A_A") (pintype "passive"))
      (node (ref "C2-3") (pin "A") (pinfunction "A_A") (pintype "passive"))
      (node (ref "C3-3") (pin "A") (pinfunction "A_A") (pintype "passive"))
      (node (ref "C4-2") (pin "C") (pinfunction "C_C") (pintype "passive"))
      (node (ref "C4-3") (pin "C") (pinfunction "C_C") (pintype "passive"))
      (node (ref "C4-4") (pin "C") (pinfunction "C_C") (pintype "passive"))
      (node (ref "C4-5") (pin "C") (pinfunction "C_C") (pintype "passive"))
      (node (ref "C4-6") (pin "C") (pinfunction "C_C") (pintype "passive"))
      (node (ref "C4-7") (pin "C") (pinfunction "C_C") (pintype "passive"))
      (node (ref "C4-8") (pin "C") (pinfunction "C_C") (pintype "passive"))
      (node (ref "C5-4") (pin "A") (pinfunction "A_A") (pintype "passive"))
      (node (ref "C6-4") (pin "A") (pinfunction "A_A") (pintype "passive"))
      (node (ref "C7-4") (pin "A") (pinfunction "A_A") (pintype "passive"))
      (node (ref "C8-4") (pin "A") (pinfunction "A_A") (pintype "passive"))
      (node (ref "U1") (pin "24") (pinfunction "CA4_24") (pintype "bidirectional"))
    )
    (net (code "6") (name "/M_CA5") (class "Default")
      (node (ref "C1-4") (pin "A") (pinfunction "A_A") (pintype "passive"))
      (node (ref "C2-4") (pin "A") (pinfunction "A_A") (pintype "passive"))
      (node (ref "C3-4") (pin "A") (pinfunction "A_A") (pintype "passive"))
      (node (ref "C4-4") (pin "A") (pinfunction "A_A") (pintype "passive"))
      (node (ref "C5-2") (pin "C") (pinfunction "C_C") (pintype "passive"))
      (node (ref "C5-3") (pin "C") (pinfunction "C_C") (pintype "passive"))
      (node (ref "C5-4") (pin "C") (pinfunction "C_C") (pintype "passive"))
      (node (ref "C5-5") (pin "C") (pinfunction "C_C") (pintype "passive"))
      (node (ref "C5-6") (pin "C") (pinfunction "C_C") (pintype "passive"))
      (node (ref "C5-7") (pin "C") (pinfunction "C_C") (pintype "passive"))
      (node (ref "C5-8") (pin "C") (pinfunction "C_C") (pintype "passive"))
      (node (ref "C6-5") (pin "A") (pinfunction "A_A") (pintype "passive"))
      (node (ref "C7-5") (pin "A") (pinfunction "A_A") (pintype "passive"))
      (node (ref "C8-5") (pin "A") (pinfunction "A_A") (pintype "passive"))
      (node (ref "U1") (pin "25") (pinfunction "CA5_25") (pintype "bidirectional"))
    )
    (net (code "7") (name "/M_CA6") (class "Default")
      (node (ref "C1-5") (pin "A") (pinfunction "A_A") (pintype "passive"))
      (node (ref "C2-5") (pin "A") (pinfunction "A_A") (pintype "passive"))
      (node (ref "C3-5") (pin "A") (pinfunction "A_A") (pintype "passive"))
      (node (ref "C4-5") (pin "A") (pinfunction "A_A") (pintype "passive"))
      (node (ref "C5-5") (pin "A") (pinfunction "A_A") (pintype "passive"))
      (node (ref "C6-2") (pin "C") (pinfunction "C_C") (pintype "passive"))
      (node (ref "C6-3") (pin "C") (pinfunction "C_C") (pintype "passive"))
      (node (ref "C6-4") (pin "C") (pinfunction "C_C") (pintype "passive"))
      (node (ref "C6-5") (pin "C") (pinfunction "C_C") (pintype "passive"))
      (node (ref "C6-6") (pin "C") (pinfunction "C_C") (pintype "passive"))
      (node (ref "C6-7") (pin "C") (pinfunction "C_C") (pintype "passive"))
      (node (ref "C6-8") (pin "C") (pinfunction "C_C") (pintype "passive"))
      (node (ref "C7-6") (pin "A") (pinfunction "A_A") (pintype "passive"))
      (node (ref "C8-6") (pin "A") (pinfunction "A_A") (pintype "passive"))
      (node (ref "U1") (pin "26") (pinfunction "CA6_26") (pintype "bidirectional"))
    )
    (net (code "8") (name "/M_CA7") (class "Default")
      (node (ref "C1-6") (pin "A") (pinfunction "A_A") (pintype "passive"))
      (node (ref "C2-6") (pin "A") (pinfunction "A_A") (pintype "passive"))
      (node (ref "C3-6") (pin "A") (pinfunction "A_A") (pintype "passive"))
      (node (ref "C4-6") (pin "A") (pinfunction "A_A") (pintype "passive"))
      (node (ref "C5-6") (pin "A") (pinfunction "A_A") (pintype "passive"))
      (node (ref "C6-6") (pin "A") (pinfunction "A_A") (pintype "passive"))
      (node (ref "C7-2") (pin "C") (pinfunction "C_C") (pintype "passive"))
      (node (ref "C7-3") (pin "C") (pinfunction "C_C") (pintype "passive"))
      (node (ref "C7-4") (pin "C") (pinfunction "C_C") (pintype "passive"))
      (node (ref "C7-5") (pin "C") (pinfunction "C_C") (pintype "passive"))
      (node (ref "C7-6") (pin "C") (pinfunction "C_C") (pintype "passive"))
      (node (ref "C7-7") (pin "C") (pinfunction "C_C") (pintype "passive"))
      (node (ref "C7-8") (pin "C") (pinfunction "C_C") (pintype "passive"))
      (node (ref "C8-7") (pin "A") (pinfunction "A_A") (pintype "passive"))
      (node (ref "U1") (pin "27") (pinfunction "CA7_27") (pintype "bidirectional"))
    )
    (net (code "9") (name "/M_CA8") (class "Default")
      (node (ref "C1-7") (pin "A") (pinfunction "A_A") (pintype "passive"))
      (node (ref "C2-7") (pin "A") (pinfunction "A_A") (pintype "passive"))
      (node (ref "C3-7") (pin "A") (pinfunction "A_A") (pintype "passive"))
      (node (ref "C4-7") (pin "A") (pinfunction "A_A") (pintype "passive"))
      (node (ref "C5-7") (pin "A") (pinfunction "A_A") (pintype "passive"))
      (node (ref "C6-7") (pin "A") (pinfunction "A_A") (pintype "passive"))
      (node (ref "C7-7") (pin "A") (pinfunction "A_A") (pintype "passive"))
      (node (ref "C8-2") (pin "C") (pinfunction "C_C") (pintype "passive"))
      (node (ref "C8-3") (pin "C") (pinfunction "C_C") (pintype "passive"))
      (node (ref "C8-4") (pin "C") (pinfunction "C_C") (pintype "passive"))
      (node (ref "C8-5") (pin "C") (pinfunction "C_C") (pintype "passive"))
      (node (ref "C8-6") (pin "C") (pinfunction "C_C") (pintype "passive"))
      (node (ref "C8-7") (pin "C") (pinfunction "C_C") (pintype "passive"))
      (node (ref "C8-8") (pin "C") (pinfunction "C_C") (pintype "passive"))
      (node (ref "U1") (pin "28") (pinfunction "CA8_28") (pintype "bidirectional"))
    )
    (net (code "10") (name "/M_CA9") (class "Default")
      (node (ref "C1-8") (pin "A") (pinfunction "A_A") (pintype "passive"))
      (node (ref "C2-8") (pin "A") (pinfunction "A_A") (pintype "passive"))
      (node (ref "C3-8") (pin "A") (pinfunction "A_A") (pintype "passive"))
      (node (ref "C4-8") (pin "A") (pinfunction "A_A") (pintype "passive"))
      (node (ref "C5-8") (pin "A") (pinfunction "A_A") (pintype "passive"))
      (node (ref "C6-8") (pin "A") (pinfunction "A_A") (pintype "passive"))
      (node (ref "C7-8") (pin "A") (pinfunction "A_A") (pintype "passive"))
      (node (ref "C8-8") (pin "A") (pinfunction "A_A") (pintype "passive"))
      (node (ref "U1") (pin "1") (pinfunction "CA9_1") (pintype "bidirectional"))
    )
    (net (code "11") (name "/M_CB1") (class "Default")
      (node (ref "C2-9") (pin "A") (pinfunction "A_A") (pintype "passive"))
      (node (ref "C3-9") (pin "A") (pinfunction "A_A") (pintype "passive"))
      (node (ref "C4-9") (pin "A") (pinfunction "A_A") (pintype "passive"))
      (node (ref "C5-9") (pin "A") (pinfunction "A_A") (pintype "passive"))
      (node (ref "C6-9") (pin "A") (pinfunction "A_A") (pintype "passive"))
      (node (ref "C7-9") (pin "A") (pinfunction "A_A") (pintype "passive"))
      (node (ref "C8-9") (pin "A") (pinfunction "A_A") (pintype "passive"))
      (node (ref "U1") (pin "7") (pinfunction "CB1_7") (pintype "bidirectional"))
    )
    (net (code "12") (name "/M_CB2") (class "Default")
      (node (ref "C2-10") (pin "C") (pinfunction "C_C") (pintype "passive"))
      (node (ref "C2-11") (pin "C") (pinfunction "C_C") (pintype "passive"))
      (node (ref "C2-12") (pin "C") (pinfunction "C_C") (pintype "passive"))
      (node (ref "C2-13") (pin "C") (pinfunction "C_C") (pintype "passive"))
      (node (ref "C2-14") (pin "C") (pinfunction "C_C") (pintype "passive"))
      (node (ref "C2-15") (pin "C") (pinfunction "C_C") (pintype "passive"))
      (node (ref "C2-9") (pin "C") (pinfunction "C_C") (pintype "passive"))
      (node (ref "C3-10") (pin "A") (pinfunction "A_A") (pintype "passive"))
      (node (ref "C4-10") (pin "A") (pinfunction "A_A") (pintype "passive"))
      (node (ref "C5-10") (pin "A") (pinfunction "A_A") (pintype "passive"))
      (node (ref "C6-10") (pin "A") (pinfunction "A_A") (pintype "passive"))
      (node (ref "C7-10") (pin "A") (pinfunction "A_A") (pintype "passive"))
      (node (ref "C8-10") (pin "A") (pinfunction "A_A") (pintype "passive"))
      (node (ref "U1") (pin "8") (pinfunction "CB2_8") (pintype "bidirectional"))
    )
    (net (code "13") (name "/M_CB3") (class "Default")
      (node (ref "C2-10") (pin "A") (pinfunction "A_A") (pintype "passive"))
      (node (ref "C3-10") (pin "C") (pinfunction "C_C") (pintype "passive"))
      (node (ref "C3-11") (pin "C") (pinfunction "C_C") (pintype "passive"))
      (node (ref "C3-12") (pin "C") (pinfunction "C_C") (pintype "passive"))
      (node (ref "C3-13") (pin "C") (pinfunction "C_C") (pintype "passive"))
      (node (ref "C3-14") (pin "C") (pinfunction "C_C") (pintype "passive"))
      (node (ref "C3-15") (pin "C") (pinfunction "C_C") (pintype "passive"))
      (node (ref "C3-9") (pin "C") (pinfunction "C_C") (pintype "passive"))
      (node (ref "C4-11") (pin "A") (pinfunction "A_A") (pintype "passive"))
      (node (ref "C5-11") (pin "A") (pinfunction "A_A") (pintype "passive"))
      (node (ref "C6-11") (pin "A") (pinfunction "A_A") (pintype "passive"))
      (node (ref "C7-11") (pin "A") (pinfunction "A_A") (pintype "passive"))
      (node (ref "C8-11") (pin "A") (pinfunction "A_A") (pintype "passive"))
      (node (ref "U1") (pin "9") (pinfunction "CB3_9") (pintype "bidirectional"))
    )
    (net (code "14") (name "/M_CB4") (class "Default")
      (node (ref "C2-11") (pin "A") (pinfunction "A_A") (pintype "passive"))
      (node (ref "C3-11") (pin "A") (pinfunction "A_A") (pintype "passive"))
      (node (ref "C4-10") (pin "C") (pinfunction "C_C") (pintype "passive"))
      (node (ref "C4-11") (pin "C") (pinfunction "C_C") (pintype "passive"))
      (node (ref "C4-12") (pin "C") (pinfunction "C_C") (pintype "passive"))
      (node (ref "C4-13") (pin "C") (pinfunction "C_C") (pintype "passive"))
      (node (ref "C4-14") (pin "C") (pinfunction "C_C") (pintype "passive"))
      (node (ref "C4-15") (pin "C") (pinfunction "C_C") (pintype "passive"))
      (node (ref "C4-9") (pin "C") (pinfunction "C_C") (pintype "passive"))
      (node (ref "C5-12") (pin "A") (pinfunction "A_A") (pintype "passive"))
      (node (ref "C6-12") (pin "A") (pinfunction "A_A") (pintype "passive"))
      (node (ref "C7-12") (pin "A") (pinfunction "A_A") (pintype "passive"))
      (node (ref "C8-12") (pin "A") (pinfunction "A_A") (pintype "passive"))
      (node (ref "U1") (pin "10") (pinfunction "CB4_10") (pintype "bidirectional"))
    )
    (net (code "15") (name "/M_CB5") (class "Default")
      (node (ref "C2-12") (pin "A") (pinfunction "A_A") (pintype "passive"))
      (node (ref "C3-12") (pin "A") (pinfunction "A_A") (pintype "passive"))
      (node (ref "C4-12") (pin "A") (pinfunction "A_A") (pintype "passive"))
      (node (ref "C5-10") (pin "C") (pinfunction "C_C") (pintype "passive"))
      (node (ref "C5-11") (pin "C") (pinfunction "C_C") (pintype "passive"))
      (node (ref "C5-12") (pin "C") (pinfunction "C_C") (pintype "passive"))
      (node (ref "C5-13") (pin "C") (pinfunction "C_C") (pintype "passive"))
      (node (ref "C5-14") (pin "C") (pinfunction "C_C") (pintype "passive"))
      (node (ref "C5-15") (pin "C") (pinfunction "C_C") (pintype "passive"))
      (node (ref "C5-9") (pin "C") (pinfunction "C_C") (pintype "passive"))
      (node (ref "C6-13") (pin "A") (pinfunction "A_A") (pintype "passive"))
      (node (ref "C7-13") (pin "A") (pinfunction "A_A") (pintype "passive"))
      (node (ref "C8-13") (pin "A") (pinfunction "A_A") (pintype "passive"))
      (node (ref "U1") (pin "11") (pinfunction "CB5_11") (pintype "bidirectional"))
    )
    (net (code "16") (name "/M_CB6") (class "Default")
      (node (ref "C2-13") (pin "A") (pinfunction "A_A") (pintype "passive"))
      (node (ref "C3-13") (pin "A") (pinfunction "A_A") (pintype "passive"))
      (node (ref "C4-13") (pin "A") (pinfunction "A_A") (pintype "passive"))
      (node (ref "C5-13") (pin "A") (pinfunction "A_A") (pintype "passive"))
      (node (ref "C6-10") (pin "C") (pinfunction "C_C") (pintype "passive"))
      (node (ref "C6-11") (pin "C") (pinfunction "C_C") (pintype "passive"))
      (node (ref "C6-12") (pin "C") (pinfunction "C_C") (pintype "passive"))
      (node (ref "C6-13") (pin "C") (pinfunction "C_C") (pintype "passive"))
      (node (ref "C6-14") (pin "C") (pinfunction "C_C") (pintype "passive"))
      (node (ref "C6-15") (pin "C") (pinfunction "C_C") (pintype "passive"))
      (node (ref "C6-9") (pin "C") (pinfunction "C_C") (pintype "passive"))
      (node (ref "C7-14") (pin "A") (pinfunction "A_A") (pintype "passive"))
      (node (ref "C8-14") (pin "A") (pinfunction "A_A") (pintype "passive"))
      (node (ref "U1") (pin "12") (pinfunction "CB6_12") (pintype "bidirectional"))
    )
    (net (code "17") (name "/M_CB7") (class "Default")
      (node (ref "C2-14") (pin "A") (pinfunction "A_A") (pintype "passive"))
      (node (ref "C3-14") (pin "A") (pinfunction "A_A") (pintype "passive"))
      (node (ref "C4-14") (pin "A") (pinfunction "A_A") (pintype "passive"))
      (node (ref "C5-14") (pin "A") (pinfunction "A_A") (pintype "passive"))
      (node (ref "C6-14") (pin "A") (pinfunction "A_A") (pintype "passive"))
      (node (ref "C7-10") (pin "C") (pinfunction "C_C") (pintype "passive"))
      (node (ref "C7-11") (pin "C") (pinfunction "C_C") (pintype "passive"))
      (node (ref "C7-12") (pin "C") (pinfunction "C_C") (pintype "passive"))
      (node (ref "C7-13") (pin "C") (pinfunction "C_C") (pintype "passive"))
      (node (ref "C7-14") (pin "C") (pinfunction "C_C") (pintype "passive"))
      (node (ref "C7-15") (pin "C") (pinfunction "C_C") (pintype "passive"))
      (node (ref "C7-9") (pin "C") (pinfunction "C_C") (pintype "passive"))
      (node (ref "C8-15") (pin "A") (pinfunction "A_A") (pintype "passive"))
      (node (ref "U1") (pin "13") (pinfunction "CB7_13") (pintype "bidirectional"))
    )
    (net (code "18") (name "/M_CB8") (class "Default")
      (node (ref "C2-15") (pin "A") (pinfunction "A_A") (pintype "passive"))
      (node (ref "C3-15") (pin "A") (pinfunction "A_A") (pintype "passive"))
      (node (ref "C4-15") (pin "A") (pinfunction "A_A") (pintype "passive"))
      (node (ref "C5-15") (pin "A") (pinfunction "A_A") (pintype "passive"))
      (node (ref "C6-15") (pin "A") (pinfunction "A_A") (pintype "passive"))
      (node (ref "C7-15") (pin "A") (pinfunction "A_A") (pintype "passive"))
      (node (ref "C8-10") (pin "C") (pinfunction "C_C") (pintype "passive"))
      (node (ref "C8-11") (pin "C") (pinfunction "C_C") (pintype "passive"))
      (node (ref "C8-12") (pin "C") (pinfunction "C_C") (pintype "passive"))
      (node (ref "C8-13") (pin "C") (pinfunction "C_C") (pintype "passive"))
      (node (ref "C8-14") (pin "C") (pinfunction "C_C") (pintype "passive"))
      (node (ref "C8-15") (pin "C") (pinfunction "C_C") (pintype "passive"))
      (node (ref "C8-9") (pin "C") (pinfunction "C_C") (pintype "passive"))
      (node (ref "U1") (pin "14") (pinfunction "CB8_14") (pintype "bidirectional"))
    )
    (net (code "19") (name "/M_INTB") (class "Default")
      (node (ref "U1") (pin "4") (pinfunction "INTB_4") (pintype "output"))
    )
    (net (code "20") (name "GND") (class "Default")
      (node (ref "C1") (pin "2") (pinfunction "2_2") (pintype "passive"))
      (node (ref "C2") (pin "2") (pinfunction "2_2") (pintype "passive"))
      (node (ref "C3") (pin "2") (pinfunction "2_2") (pintype "passive"))
      (node (ref "C4") (pin "2") (pinfunction "2_2") (pintype "passive"))
      (node (ref "C5") (pin "2") (pinfunction "2_2") (pintype "passive"))
      (node (ref "GND") (pin "TP") (pinfunction "TP_TP") (pintype "input"))
      (node (ref "K1") (pin "2") (pinfunction "P$2_2") (pintype "bidirectional"))
      (node (ref "R7") (pin "2") (pinfunction "2_2") (pintype "passive"))
      (node (ref "R8") (pin "1") (pinfunction "1_1") (pintype "passive"))
      (node (ref "S1") (pin "1") (pinfunction "NO_1") (pintype "bidirectional"))
      (node (ref "S2") (pin "1") (pinfunction "NO_1") (pintype "bidirectional"))
      (node (ref "U1") (pin "5") (pinfunction "GND_5") (pintype "power_in"))
      (node (ref "U1") (pin "THERMAL") (pinfunction "GND_THERMAL") (pintype "power_in"))
    )
    (net (code "21") (name "M_SCL") (class "Default")
      (node (ref "K1") (pin "4") (pinfunction "P$4_4") (pintype "bidirectional"))
      (node (ref "M_SCL") (pin "TP") (pinfunction "TP_TP") (pintype "input"))
      (node (ref "R6") (pin "1") (pinfunction "1_1") (pintype "passive"))
      (node (ref "U1") (pin "20") (pinfunction "SCL_20") (pintype "bidirectional"))
    )
    (net (code "22") (name "M_SDA") (class "Default")
      (node (ref "K1") (pin "3") (pinfunction "P$3_3") (pintype "bidirectional"))
      (node (ref "M_SDA") (pin "TP") (pinfunction "TP_TP") (pintype "input"))
      (node (ref "R4") (pin "1") (pinfunction "1_1") (pintype "passive"))
      (node (ref "U1") (pin "19") (pinfunction "SDA_19") (pintype "bidirectional"))
    )
    (net (code "23") (name "Net-(S1-COM)") (class "Default")
      (node (ref "C2") (pin "1") (pinfunction "1_1") (pintype "passive"))
      (node (ref "R1") (pin "1") (pinfunction "1_1") (pintype "passive"))
      (node (ref "R3") (pin "1") (pinfunction "1_1") (pintype "passive"))
      (node (ref "S1") (pin "2") (pinfunction "COM_2") (pintype "bidirectional"))
    )
    (net (code "24") (name "Net-(S2-COM)") (class "Default")
      (node (ref "C3") (pin "1") (pinfunction "1_1") (pintype "passive"))
      (node (ref "R2") (pin "1") (pinfunction "1_1") (pintype "passive"))
      (node (ref "R5") (pin "1") (pinfunction "1_1") (pintype "passive"))
      (node (ref "S2") (pin "2") (pinfunction "COM_2") (pintype "bidirectional"))
    )
    (net (code "25") (name "Net-(U1-R_EXT)") (class "Default")
      (node (ref "R8") (pin "2") (pinfunction "2_2") (pintype "passive"))
      (node (ref "U1") (pin "6") (pinfunction "R_EXT_6") (pintype "bidirectional"))
    )
    (net (code "26") (name "S_DOWN") (class "Default")
      (node (ref "K1") (pin "6") (pinfunction "P$6_6") (pintype "bidirectional"))
      (node (ref "R5") (pin "2") (pinfunction "2_2") (pintype "passive"))
      (node (ref "S_DOWN") (pin "TP") (pinfunction "TP_TP") (pintype "input"))
    )
    (net (code "27") (name "S_UP") (class "Default")
      (node (ref "K1") (pin "5") (pinfunction "P$5_5") (pintype "bidirectional"))
      (node (ref "R3") (pin "2") (pinfunction "2_2") (pintype "passive"))
      (node (ref "S_UP") (pin "TP") (pinfunction "TP_TP") (pintype "input"))
    )
    (net (code "28") (name "VCC") (class "Default")
      (node (ref "C1") (pin "1") (pinfunction "1_1") (pintype "passive"))
      (node (ref "C4") (pin "1") (pinfunction "1_1") (pintype "passive"))
      (node (ref "C5") (pin "1") (pinfunction "1_1") (pintype "passive"))
      (node (ref "K1") (pin "1") (pinfunction "P$1_1") (pintype "bidirectional"))
      (node (ref "R1") (pin "2") (pinfunction "2_2") (pintype "passive"))
      (node (ref "R2") (pin "2") (pinfunction "2_2") (pintype "passive"))
      (node (ref "R4") (pin "2") (pinfunction "2_2") (pintype "passive"))
      (node (ref "R6") (pin "2") (pinfunction "2_2") (pintype "passive"))
      (node (ref "U1") (pin "2") (pinfunction "VCC_2") (pintype "power_in"))
      (node (ref "U1") (pin "3") (pinfunction "SHUTDOWN_3") (pintype "input"))
      (node (ref "VCC") (pin "TP") (pinfunction "TP_TP") (pintype "input"))
    )
    (net (code "29") (name "unconnected-(U1-AUDIOIN-Pad17)") (class "Default")
      (node (ref "U1") (pin "17") (pinfunction "AUDIOIN_17") (pintype "input"))
    )
    (net (code "30") (name "unconnected-(U1-CB9-Pad15)") (class "Default")
      (node (ref "U1") (pin "15") (pinfunction "CB9_15") (pintype "bidirectional"))
    )
    (net (code "31") (name "unconnected-(U1-C_FILT-Pad16)") (class "Default")
      (node (ref "U1") (pin "16") (pinfunction "C_FILT_16") (pintype "bidirectional"))
    )
  )
)
